# Ate_RF_Sch.net
KiCad netlist of a schematic drawn in Altium Designer
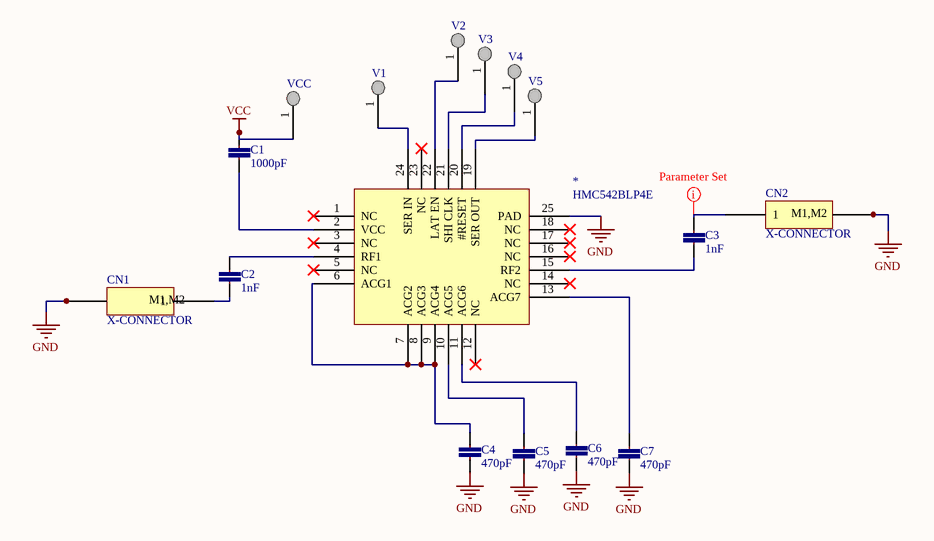
[diagram p0: Ate_RF_Sch.SchDoc]

(export (version "E")
  (design (tool "Eeschema 10.0.6"))
  (components
    (comp (ref "*")
      (value "HMC542BLP4E")
      (footprint "QFN50P400X400X80_HS-25N")
      (description "Attenuators DATT, 0.5 dB LSB 6 Bit (Hitt Controller)")
      (libsource (lib "IMBEL") (part "HMC542BLP4E"))
    )
    (comp (ref "C1")
      (value "1000pF")
      (footprint "CAPC0603(1608)55_L")
      (description "CAP CER 1000PF 50V C0G/NP0 0603")
      (fields (field (name "PART NO") "GRM1885C1H102JA01D"))
      (libsource (lib "IMBEL") (part "CAPACITOR"))
    )
    (comp (ref "C2")
      (value "1nF")
      (footprint "0402-CAP")
      (description "CAP CER 1000pF 25V 10% X7R 0402")
      (fields (field (name "PART NO") "VJ0402Y562KNAAJ"))
      (libsource (lib "IMBEL") (part "CAPACITOR"))
    )
    (comp (ref "C3")
      (value "1nF")
      (footprint "0402-CAP")
      (description "CAP CER 1000pF 25V 10% X7R 0402")
      (fields (field (name "PART NO") "VJ0402Y562KNAAJ"))
      (libsource (lib "IMBEL") (part "CAPACITOR"))
    )
    (comp (ref "C4")
      (value "470pF")
      (footprint "0402-CAP")
      (description "CAP CER 470PF 50V C0G/NP0 0402")
      (fields (field (name "PART NO") "GRM1555C1H471JA01D"))
      (libsource (lib "IMBEL") (part "CAPACITOR"))
    )
    (comp (ref "C5")
      (value "470pF")
      (footprint "0402-CAP")
      (description "CAP CER 470PF 50V C0G/NP0 0402")
      (fields (field (name "PART NO") "GRM1555C1H471JA01D"))
      (libsource (lib "IMBEL") (part "CAPACITOR"))
    )
    (comp (ref "C6")
      (value "470pF")
      (footprint "0402-CAP")
      (description "CAP CER 470PF 50V C0G/NP0 0402")
      (fields (field (name "PART NO") "GRM1555C1H471JA01D"))
      (libsource (lib "IMBEL") (part "CAPACITOR"))
    )
    (comp (ref "C7")
      (value "470pF")
      (footprint "0402-CAP")
      (description "CAP CER 470PF 50V C0G/NP0 0402")
      (fields (field (name "PART NO") "GRM1555C1H471JA01D"))
      (libsource (lib "IMBEL") (part "CAPACITOR"))
    )
    (comp (ref "CN1")
      (value "X-CONNECTOR")
      (footprint "X-CONNECTOR-PCB")
      (description "CONECTOR PARA MÓDULOS X MICROWAVE")
      (libsource (lib "") (part "X-CONNECTOR_1"))
    )
    (comp (ref "CN2")
      (value "X-CONNECTOR")
      (footprint "X-CONNECTOR-PCB")
      (description "CONECTOR PARA MÓDULOS X MICROWAVE")
      (libsource (lib "(LR)²") (part "X-CONNECTOR"))
    )
    (comp (ref "V1")
      (value "TEST_VIA_RF")
      (footprint "New footprint 1")
      (description "Test VIA for RF circuits")
      (libsource (lib "IMBEL") (part "TEST_VIA"))
    )
    (comp (ref "V2")
      (value "TEST_VIA_RF")
      (footprint "New footprint 1")
      (description "Test VIA for RF circuits")
      (libsource (lib "IMBEL") (part "TEST_VIA"))
    )
    (comp (ref "V3")
      (value "TEST_VIA_RF")
      (footprint "New footprint 1")
      (description "Test VIA for RF circuits")
      (libsource (lib "IMBEL") (part "TEST_VIA"))
    )
    (comp (ref "V4")
      (value "TEST_VIA_RF")
      (footprint "New footprint 1")
      (description "Test VIA for RF circuits")
      (libsource (lib "IMBEL") (part "TEST_VIA"))
    )
    (comp (ref "V5")
      (value "TEST_VIA_RF")
      (footprint "New footprint 1")
      (description "Test VIA for RF circuits")
      (libsource (lib "IMBEL") (part "TEST_VIA"))
    )
    (comp (ref "VCC")
      (value "TEST_VIA_RF")
      (footprint "New footprint 1")
      (description "Test VIA for RF circuits")
      (libsource (lib "IMBEL") (part "TEST_VIA"))
    )
  )
  (nets
    (net (code "1") (name "GND") (class "Default")
      (node (ref "*") (pin "25") (pinfunction "PAD_25") (pintype "passive"))
      (node (ref "C4") (pin "2") (pinfunction "2_2") (pintype "passive"))
      (node (ref "C5") (pin "2") (pinfunction "2_2") (pintype "passive"))
      (node (ref "C6") (pin "2") (pinfunction "2_2") (pintype "passive"))
      (node (ref "C7") (pin "2") (pinfunction "2_2") (pintype "passive"))
      (node (ref "CN1") (pin "M1") (pinfunction "M1_M1") (pintype "passive"))
      (node (ref "CN1") (pin "M2") (pinfunction "M2_M2") (pintype "passive"))
      (node (ref "CN2") (pin "M1") (pinfunction "M1_M1") (pintype "passive"))
      (node (ref "CN2") (pin "M2") (pinfunction "M2_M2") (pintype "passive"))
    )
    (net (code "2") (name "Net-(*-#RESET)") (class "Default")
      (node (ref "*") (pin "20") (pinfunction "#RESET_20") (pintype "passive"))
      (node (ref "V4") (pin "1") (pinfunction "1_1") (pintype "passive"))
    )
    (net (code "3") (name "Net-(*-ACG1)") (class "Default")
      (node (ref "*") (pin "6") (pinfunction "ACG1_6") (pintype "passive"))
      (node (ref "*") (pin "7") (pinfunction "ACG2_7") (pintype "passive"))
      (node (ref "*") (pin "8") (pinfunction "ACG3_8") (pintype "passive"))
      (node (ref "*") (pin "9") (pinfunction "ACG4_9") (pintype "passive"))
      (node (ref "C4") (pin "1") (pinfunction "1_1") (pintype "passive"))
    )
    (net (code "4") (name "Net-(*-ACG5)") (class "Default")
      (node (ref "*") (pin "10") (pinfunction "ACG5_10") (pintype "passive"))
      (node (ref "C5") (pin "1") (pinfunction "1_1") (pintype "passive"))
    )
    (net (code "5") (name "Net-(*-ACG6)") (class "Default")
      (node (ref "*") (pin "11") (pinfunction "ACG6_11") (pintype "passive"))
      (node (ref "C6") (pin "1") (pinfunction "1_1") (pintype "passive"))
    )
    (net (code "6") (name "Net-(*-ACG7)") (class "Default")
      (node (ref "*") (pin "13") (pinfunction "ACG7_13") (pintype "passive"))
      (node (ref "C7") (pin "1") (pinfunction "1_1") (pintype "passive"))
    )
    (net (code "7") (name "Net-(*-LAT_EN)") (class "Default")
      (node (ref "*") (pin "22") (pinfunction "LAT_EN_22") (pintype "passive"))
      (node (ref "V2") (pin "1") (pinfunction "1_1") (pintype "passive"))
    )
    (net (code "8") (name "Net-(*-RF1)") (class "Default")
      (node (ref "*") (pin "4") (pinfunction "RF1_4") (pintype "passive"))
      (node (ref "C2") (pin "1") (pinfunction "1_1") (pintype "passive"))
    )
    (net (code "9") (name "Net-(*-RF2)") (class "Default")
      (node (ref "*") (pin "15") (pinfunction "RF2_15") (pintype "passive"))
      (node (ref "C3") (pin "2") (pinfunction "2_2") (pintype "passive"))
    )
    (net (code "10") (name "Net-(*-SER_IN)") (class "Default")
      (node (ref "*") (pin "24") (pinfunction "SER_IN_24") (pintype "passive"))
      (node (ref "V1") (pin "1") (pinfunction "1_1") (pintype "passive"))
    )
    (net (code "11") (name "Net-(*-SER_OUT)") (class "Default")
      (node (ref "*") (pin "19") (pinfunction "SER_OUT_19") (pintype "passive"))
      (node (ref "V5") (pin "1") (pinfunction "1_1") (pintype "passive"))
    )
    (net (code "12") (name "Net-(*-SHI_CLK)") (class "Default")
      (node (ref "*") (pin "21") (pinfunction "SHI_CLK_21") (pintype "passive"))
      (node (ref "V3") (pin "1") (pinfunction "1_1") (pintype "passive"))
    )
    (net (code "13") (name "Net-(*-VCC)") (class "Default")
      (node (ref "*") (pin "2") (pinfunction "VCC_2") (pintype "passive"))
      (node (ref "C1") (pin "2") (pinfunction "2_2") (pintype "passive"))
    )
    (net (code "14") (name "Net-(C2-Pad2)") (class "Default")
      (node (ref "C2") (pin "2") (pinfunction "2_2") (pintype "passive"))
      (node (ref "CN1") (pin "1") (pinfunction "1_1") (pintype "passive"))
    )
    (net (code "15") (name "Net-(C3-Pad1)") (class "Default")
      (node (ref "C3") (pin "1") (pinfunction "1_1") (pintype "passive"))
      (node (ref "CN2") (pin "1") (pinfunction "1_1") (pintype "passive"))
    )
    (net (code "16") (name "VCC") (class "Default")
      (node (ref "C1") (pin "1") (pinfunction "1_1") (pintype "passive"))
      (node (ref "VCC") (pin "1") (pinfunction "1_1") (pintype "passive"))
    )
    (net (code "17") (name "unconnected-(*-NC-Pad1)") (class "Default")
      (node (ref "*") (pin "1") (pinfunction "NC_1") (pintype "passive+no_connect"))
    )
    (net (code "18") (name "unconnected-(*-NC-Pad3)") (class "Default")
      (node (ref "*") (pin "3") (pinfunction "NC_3") (pintype "passive+no_connect"))
    )
    (net (code "19") (name "unconnected-(*-NC-Pad5)") (class "Default")
      (node (ref "*") (pin "5") (pinfunction "NC_5") (pintype "passive+no_connect"))
    )
    (net (code "20") (name "unconnected-(*-NC-Pad12)") (class "Default")
      (node (ref "*") (pin "12") (pinfunction "NC_12") (pintype "passive+no_connect"))
    )
    (net (code "21") (name "unconnected-(*-NC-Pad14)") (class "Default")
      (node (ref "*") (pin "14") (pinfunction "NC_14") (pintype "passive+no_connect"))
    )
    (net (code "22") (name "unconnected-(*-NC-Pad16)") (class "Default")
      (node (ref "*") (pin "16") (pinfunction "NC_16") (pintype "passive+no_connect"))
    )
    (net (code "23") (name "unconnected-(*-NC-Pad17)") (class "Default")
      (node (ref "*") (pin "17") (pinfunction "NC_17") (pintype "passive+no_connect"))
    )
    (net (code "24") (name "unconnected-(*-NC-Pad18)") (class "Default")
      (node (ref "*") (pin "18") (pinfunction "NC_18") (pintype "passive+no_connect"))
    )
    (net (code "25") (name "unconnected-(*-NC-Pad23)") (class "Default")
      (node (ref "*") (pin "23") (pinfunction "NC_23") (pintype "passive+no_connect"))
    )
  )
)
